# sensor.net
KiCad netlist of a schematic drawn in Altium Designer
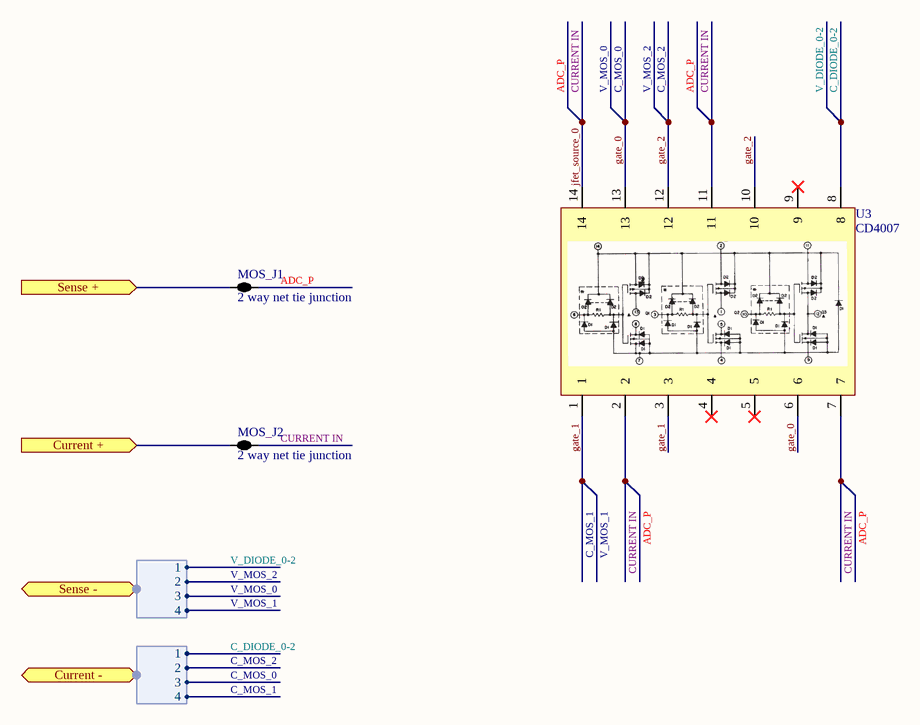
[diagram p0: sensor.SchDoc]

(export (version "E")
  (design (tool "Eeschema 10.0.6"))
  (components
    (comp (ref "MOS_J1")
      (value "2 way net tie junction")
      (footprint "2way_LP")
      (libsource (lib "NetTieLib") (part "2way"))
    )
    (comp (ref "MOS_J2")
      (value "2 way net tie junction")
      (footprint "2way_LP")
      (libsource (lib "NetTieLib") (part "2way"))
    )
    (comp (ref "U3")
      (value "CD4007")
      (footprint "TSSOP14")
      (description "CMOS Dual Complementary Pair Plus Inverter")
      (libsource (lib "transistors") (part "CD4007"))
    )
  )
  (nets
    (net (code "2") (name "/ADC_P") (class "Default")
      (node (ref "MOS_J1") (pin "2") (pinfunction "2_2") (pintype "passive"))
      (node (ref "MOS_J2") (pin "2") (pinfunction "2_2") (pintype "passive"))
      (node (ref "U3") (pin "11") (pinfunction "11_11") (pintype "passive"))
      (node (ref "U3") (pin "14") (pinfunction "14_14") (pintype "passive"))
      (node (ref "U3") (pin "2") (pinfunction "2_2") (pintype "passive"))
      (node (ref "U3") (pin "7") (pinfunction "7_7") (pintype "passive"))
    )
    (net (code "3") (name "/C_DIODE_0-2") (class "Default")
      (node (ref "U3") (pin "8") (pinfunction "8_8") (pintype "passive"))
    )
    (net (code "4") (name "/C_MOS_0") (class "Default")
      (node (ref "U3") (pin "13") (pinfunction "13_13") (pintype "passive"))
      (node (ref "U3") (pin "6") (pinfunction "6_6") (pintype "passive"))
    )
    (net (code "5") (name "/C_MOS_1") (class "Default")
      (node (ref "U3") (pin "1") (pinfunction "1_1") (pintype "passive"))
      (node (ref "U3") (pin "3") (pinfunction "3_3") (pintype "passive"))
    )
    (net (code "6") (name "/C_MOS_2") (class "Default")
      (node (ref "U3") (pin "10") (pinfunction "10_10") (pintype "passive"))
      (node (ref "U3") (pin "12") (pinfunction "12_12") (pintype "passive"))
    )
    (net (code "7") (name "/Current +") (class "Default")
      (node (ref "MOS_J2") (pin "1") (pinfunction "1_1") (pintype "passive"))
    )
    (net (code "8") (name "/Sense +") (class "Default")
      (node (ref "MOS_J1") (pin "1") (pinfunction "1_1") (pintype "passive"))
    )
    (net (code "10") (name "unconnected-(U3-Pad4)") (class "Default")
      (node (ref "U3") (pin "4") (pinfunction "4_4") (pintype "passive+no_connect"))
    )
    (net (code "11") (name "unconnected-(U3-Pad5)") (class "Default")
      (node (ref "U3") (pin "5") (pinfunction "5_5") (pintype "passive+no_connect"))
    )
    (net (code "12") (name "unconnected-(U3-Pad9)") (class "Default")
      (node (ref "U3") (pin "9") (pinfunction "9_9") (pintype "passive+no_connect"))
    )
  )
)
